# SaltwatersEchoControls.net
KiCad netlist of a schematic drawn in EAGLE
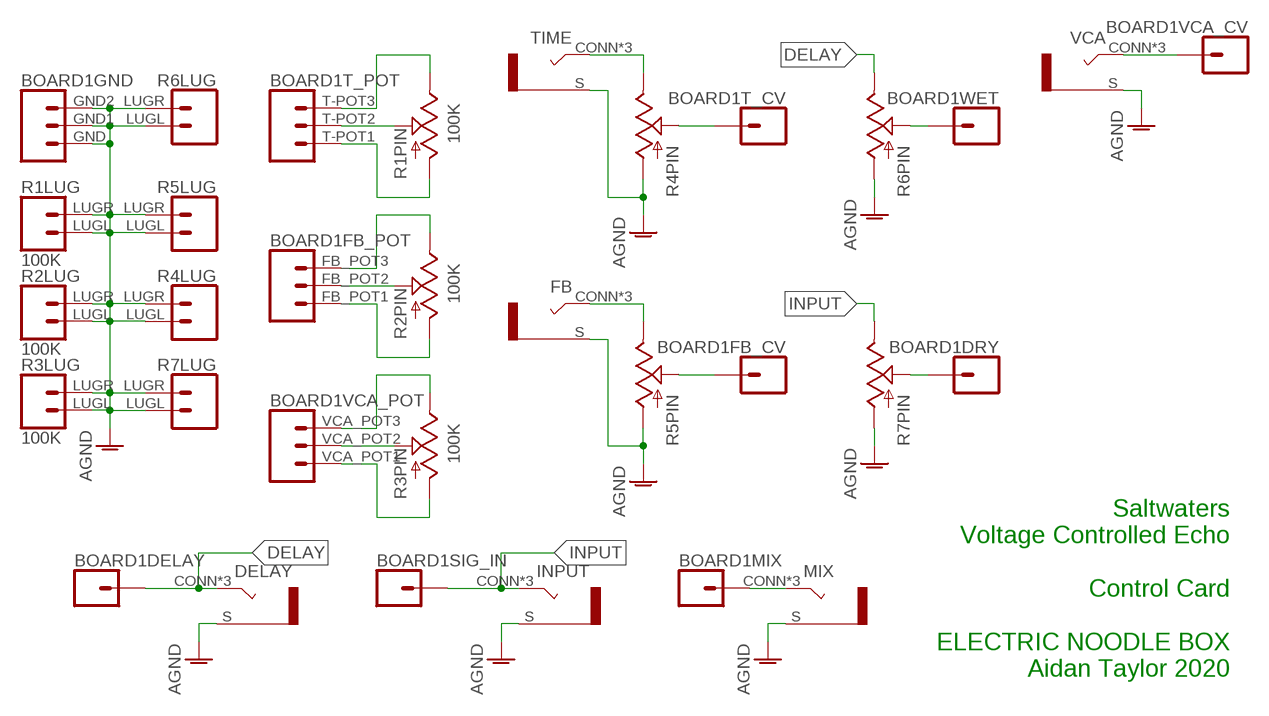
[diagram p0: schematic, sheet 1]

(export (version "E")
  (design (tool "Eeschema 10.0.6"))
  (components
    (comp (ref "BOARD1")
      (value "SALTWATERS_LINK")
      (footprint "eagle-import:SALTWATERS")
      (libsource (lib "eagle-import") (part "SALTWATERS_LINK"))
    )
    (comp (ref "DELAY")
      (value "COMBI-JACKCINCHNANA")
      (footprint "eagle-import:NEWCOMBOJACK_PANEL")
      (libsource (lib "eagle-import") (part "COMBI-JACKCINCHNANA"))
    )
    (comp (ref "FB")
      (value "COMBI-JACKCINCHNANA")
      (footprint "eagle-import:NEWCOMBOJACK_PANEL")
      (libsource (lib "eagle-import") (part "COMBI-JACKCINCHNANA"))
    )
    (comp (ref "INPUT")
      (value "COMBI-JACKCINCHNANA")
      (footprint "eagle-import:NEWCOMBOJACK_PANEL")
      (libsource (lib "eagle-import") (part "COMBI-JACKCINCHNANA"))
    )
    (comp (ref "MIX")
      (value "COMBI-JACKCINCHNANA")
      (footprint "eagle-import:NEWCOMBOJACK_PANEL")
      (libsource (lib "eagle-import") (part "COMBI-JACKCINCHNANA"))
    )
    (comp (ref "R1")
      (value "100K")
      (footprint "eagle-import:ALPHA_RV09_9MMPOT")
      (libsource (lib "eagle-import") (part "POTENTIOMETER"))
    )
    (comp (ref "R2")
      (value "100K")
      (footprint "eagle-import:ALPHA_RV09_9MMPOT")
      (libsource (lib "eagle-import") (part "POTENTIOMETER"))
    )
    (comp (ref "R3")
      (value "100K")
      (footprint "eagle-import:ALPHA_RV09_9MMPOT")
      (libsource (lib "eagle-import") (part "POTENTIOMETER"))
    )
    (comp (ref "R4")
      (value "POTENTIOMETER")
      (footprint "eagle-import:ALPHA_RV09_9MMPOT")
      (libsource (lib "eagle-import") (part "POTENTIOMETER"))
    )
    (comp (ref "R5")
      (value "POTENTIOMETER")
      (footprint "eagle-import:ALPHA_RV09_9MMPOT")
      (libsource (lib "eagle-import") (part "POTENTIOMETER"))
    )
    (comp (ref "R6")
      (value "POTENTIOMETER")
      (footprint "eagle-import:ALPHA_RV09_9MMPOT")
      (libsource (lib "eagle-import") (part "POTENTIOMETER"))
    )
    (comp (ref "R7")
      (value "POTENTIOMETER")
      (footprint "eagle-import:ALPHA_RV09_9MMPOT")
      (libsource (lib "eagle-import") (part "POTENTIOMETER"))
    )
    (comp (ref "TIME")
      (value "COMBI-JACKCINCHNANA")
      (footprint "eagle-import:NEWCOMBOJACK_PANEL")
      (libsource (lib "eagle-import") (part "COMBI-JACKCINCHNANA"))
    )
    (comp (ref "VCA")
      (value "COMBI-JACKCINCHNANA")
      (footprint "eagle-import:NEWCOMBOJACK_PANEL")
      (libsource (lib "eagle-import") (part "COMBI-JACKCINCHNANA"))
    )
  )
  (nets
    (net (code "1") (name "AGND") (class "Default")
      (node (ref "BOARD1") (pin "GND") (pinfunction "1_GND") (pintype "passive"))
      (node (ref "BOARD1") (pin "GND1") (pinfunction "2_GND1") (pintype "passive"))
      (node (ref "BOARD1") (pin "GND2") (pinfunction "3_GND2") (pintype "passive"))
      (node (ref "DELAY") (pin "S") (pinfunction "S_S") (pintype "passive"))
      (node (ref "FB") (pin "S") (pinfunction "S_S") (pintype "passive"))
      (node (ref "INPUT") (pin "S") (pinfunction "S_S") (pintype "passive"))
      (node (ref "MIX") (pin "S") (pinfunction "S_S") (pintype "passive"))
      (node (ref "R1") (pin "LUGL") (pinfunction "1_LUGL") (pintype "passive"))
      (node (ref "R1") (pin "LUGR") (pinfunction "2_LUGR") (pintype "passive"))
      (node (ref "R2") (pin "LUGL") (pinfunction "1_LUGL") (pintype "passive"))
      (node (ref "R2") (pin "LUGR") (pinfunction "2_LUGR") (pintype "passive"))
      (node (ref "R3") (pin "LUGL") (pinfunction "1_LUGL") (pintype "passive"))
      (node (ref "R3") (pin "LUGR") (pinfunction "2_LUGR") (pintype "passive"))
      (node (ref "R4") (pin "C1") (pinfunction "A_C1") (pintype "passive"))
      (node (ref "R4") (pin "LUGL") (pinfunction "1_LUGL") (pintype "passive"))
      (node (ref "R4") (pin "LUGR") (pinfunction "2_LUGR") (pintype "passive"))
      (node (ref "R5") (pin "C1") (pinfunction "A_C1") (pintype "passive"))
      (node (ref "R5") (pin "LUGL") (pinfunction "1_LUGL") (pintype "passive"))
      (node (ref "R5") (pin "LUGR") (pinfunction "2_LUGR") (pintype "passive"))
      (node (ref "R6") (pin "C1") (pinfunction "A_C1") (pintype "passive"))
      (node (ref "R6") (pin "LUGL") (pinfunction "1_LUGL") (pintype "passive"))
      (node (ref "R6") (pin "LUGR") (pinfunction "2_LUGR") (pintype "passive"))
      (node (ref "R7") (pin "C1") (pinfunction "A_C1") (pintype "passive"))
      (node (ref "R7") (pin "LUGL") (pinfunction "1_LUGL") (pintype "passive"))
      (node (ref "R7") (pin "LUGR") (pinfunction "2_LUGR") (pintype "passive"))
      (node (ref "TIME") (pin "S") (pinfunction "S_S") (pintype "passive"))
      (node (ref "VCA") (pin "S") (pinfunction "S_S") (pintype "passive"))
    )
    (net (code "2") (name "DELAY") (class "Default")
      (node (ref "BOARD1") (pin "DELAY") (pinfunction "1_DELAY") (pintype "passive"))
      (node (ref "DELAY") (pin "CONN") (pinfunction "T_CONN") (pintype "passive"))
      (node (ref "DELAY") (pin "T1") (pinfunction "T_T1") (pintype "passive"))
      (node (ref "DELAY") (pin "T2") (pinfunction "T_T2") (pintype "passive"))
      (node (ref "R6") (pin "C3") (pinfunction "B_C3") (pintype "passive"))
    )
    (net (code "3") (name "INPUT") (class "Default")
      (node (ref "BOARD1") (pin "SIG_IN") (pinfunction "1_SIG_IN") (pintype "passive"))
      (node (ref "INPUT") (pin "CONN") (pinfunction "T_CONN") (pintype "passive"))
      (node (ref "INPUT") (pin "T1") (pinfunction "T_T1") (pintype "passive"))
      (node (ref "INPUT") (pin "T2") (pinfunction "T_T2") (pintype "passive"))
      (node (ref "R7") (pin "C3") (pinfunction "B_C3") (pintype "passive"))
    )
    (net (code "4") (name "Net-(BOARD1B-1)") (class "Default")
      (node (ref "BOARD1") (pin "DRY") (pinfunction "1_DRY") (pintype "passive"))
      (node (ref "R7") (pin "C2") (pinfunction "W_C2") (pintype "passive"))
    )
    (net (code "5") (name "Net-(BOARD1C-1)") (class "Default")
      (node (ref "BOARD1") (pin "FB_CV") (pinfunction "1_FB_CV") (pintype "passive"))
      (node (ref "R5") (pin "C2") (pinfunction "W_C2") (pintype "passive"))
    )
    (net (code "6") (name "Net-(BOARD1D-1)") (class "Default")
      (node (ref "BOARD1") (pin "FB_POT1") (pinfunction "1_FB_POT1") (pintype "passive"))
      (node (ref "R2") (pin "C1") (pinfunction "A_C1") (pintype "passive"))
    )
    (net (code "7") (name "Net-(BOARD1D-2)") (class "Default")
      (node (ref "BOARD1") (pin "FB_POT2") (pinfunction "2_FB_POT2") (pintype "passive"))
      (node (ref "R2") (pin "C2") (pinfunction "W_C2") (pintype "passive"))
    )
    (net (code "8") (name "Net-(BOARD1D-3)") (class "Default")
      (node (ref "BOARD1") (pin "FB_POT3") (pinfunction "3_FB_POT3") (pintype "passive"))
      (node (ref "R2") (pin "C3") (pinfunction "B_C3") (pintype "passive"))
    )
    (net (code "9") (name "Net-(BOARD1F-1)") (class "Default")
      (node (ref "BOARD1") (pin "MIX") (pinfunction "1_MIX") (pintype "passive"))
      (node (ref "MIX") (pin "CONN") (pinfunction "T_CONN") (pintype "passive"))
      (node (ref "MIX") (pin "T1") (pinfunction "T_T1") (pintype "passive"))
      (node (ref "MIX") (pin "T2") (pinfunction "T_T2") (pintype "passive"))
    )
    (net (code "10") (name "Net-(BOARD1H-1)") (class "Default")
      (node (ref "BOARD1") (pin "T_CV") (pinfunction "1_T_CV") (pintype "passive"))
      (node (ref "R4") (pin "C2") (pinfunction "W_C2") (pintype "passive"))
    )
    (net (code "11") (name "Net-(BOARD1I-1)") (class "Default")
      (node (ref "BOARD1") (pin "T-POT1") (pinfunction "1_T-POT1") (pintype "passive"))
      (node (ref "R1") (pin "C1") (pinfunction "A_C1") (pintype "passive"))
    )
    (net (code "12") (name "Net-(BOARD1I-2)") (class "Default")
      (node (ref "BOARD1") (pin "T-POT2") (pinfunction "2_T-POT2") (pintype "passive"))
      (node (ref "R1") (pin "C2") (pinfunction "W_C2") (pintype "passive"))
    )
    (net (code "13") (name "Net-(BOARD1I-3)") (class "Default")
      (node (ref "BOARD1") (pin "T-POT3") (pinfunction "3_T-POT3") (pintype "passive"))
      (node (ref "R1") (pin "C3") (pinfunction "B_C3") (pintype "passive"))
    )
    (net (code "14") (name "Net-(BOARD1J-1)") (class "Default")
      (node (ref "BOARD1") (pin "VCA_CV") (pinfunction "1_VCA_CV") (pintype "passive"))
      (node (ref "VCA") (pin "CONN") (pinfunction "T_CONN") (pintype "passive"))
      (node (ref "VCA") (pin "T1") (pinfunction "T_T1") (pintype "passive"))
      (node (ref "VCA") (pin "T2") (pinfunction "T_T2") (pintype "passive"))
    )
    (net (code "15") (name "Net-(BOARD1K-1)") (class "Default")
      (node (ref "BOARD1") (pin "VCA_POT1") (pinfunction "1_VCA_POT1") (pintype "passive"))
      (node (ref "R3") (pin "C1") (pinfunction "A_C1") (pintype "passive"))
    )
    (net (code "16") (name "Net-(BOARD1K-2)") (class "Default")
      (node (ref "BOARD1") (pin "VCA_POT2") (pinfunction "2_VCA_POT2") (pintype "passive"))
      (node (ref "R3") (pin "C2") (pinfunction "W_C2") (pintype "passive"))
    )
    (net (code "17") (name "Net-(BOARD1K-3)") (class "Default")
      (node (ref "BOARD1") (pin "VCA_POT3") (pinfunction "3_VCA_POT3") (pintype "passive"))
      (node (ref "R3") (pin "C3") (pinfunction "B_C3") (pintype "passive"))
    )
    (net (code "18") (name "Net-(BOARD1L-1)") (class "Default")
      (node (ref "BOARD1") (pin "WET") (pinfunction "1_WET") (pintype "passive"))
      (node (ref "R6") (pin "C2") (pinfunction "W_C2") (pintype "passive"))
    )
    (net (code "19") (name "Net-(R4B-B)") (class "Default")
      (node (ref "R4") (pin "C3") (pinfunction "B_C3") (pintype "passive"))
      (node (ref "TIME") (pin "CONN") (pinfunction "T_CONN") (pintype "passive"))
      (node (ref "TIME") (pin "T1") (pinfunction "T_T1") (pintype "passive"))
      (node (ref "TIME") (pin "T2") (pinfunction "T_T2") (pintype "passive"))
    )
    (net (code "20") (name "Net-(R5B-B)") (class "Default")
      (node (ref "FB") (pin "CONN") (pinfunction "T_CONN") (pintype "passive"))
      (node (ref "FB") (pin "T1") (pinfunction "T_T1") (pintype "passive"))
      (node (ref "FB") (pin "T2") (pinfunction "T_T2") (pintype "passive"))
      (node (ref "R5") (pin "C3") (pinfunction "B_C3") (pintype "passive"))
    )
  )
)
